# Power.net
KiCad netlist of a schematic drawn in Altium Designer
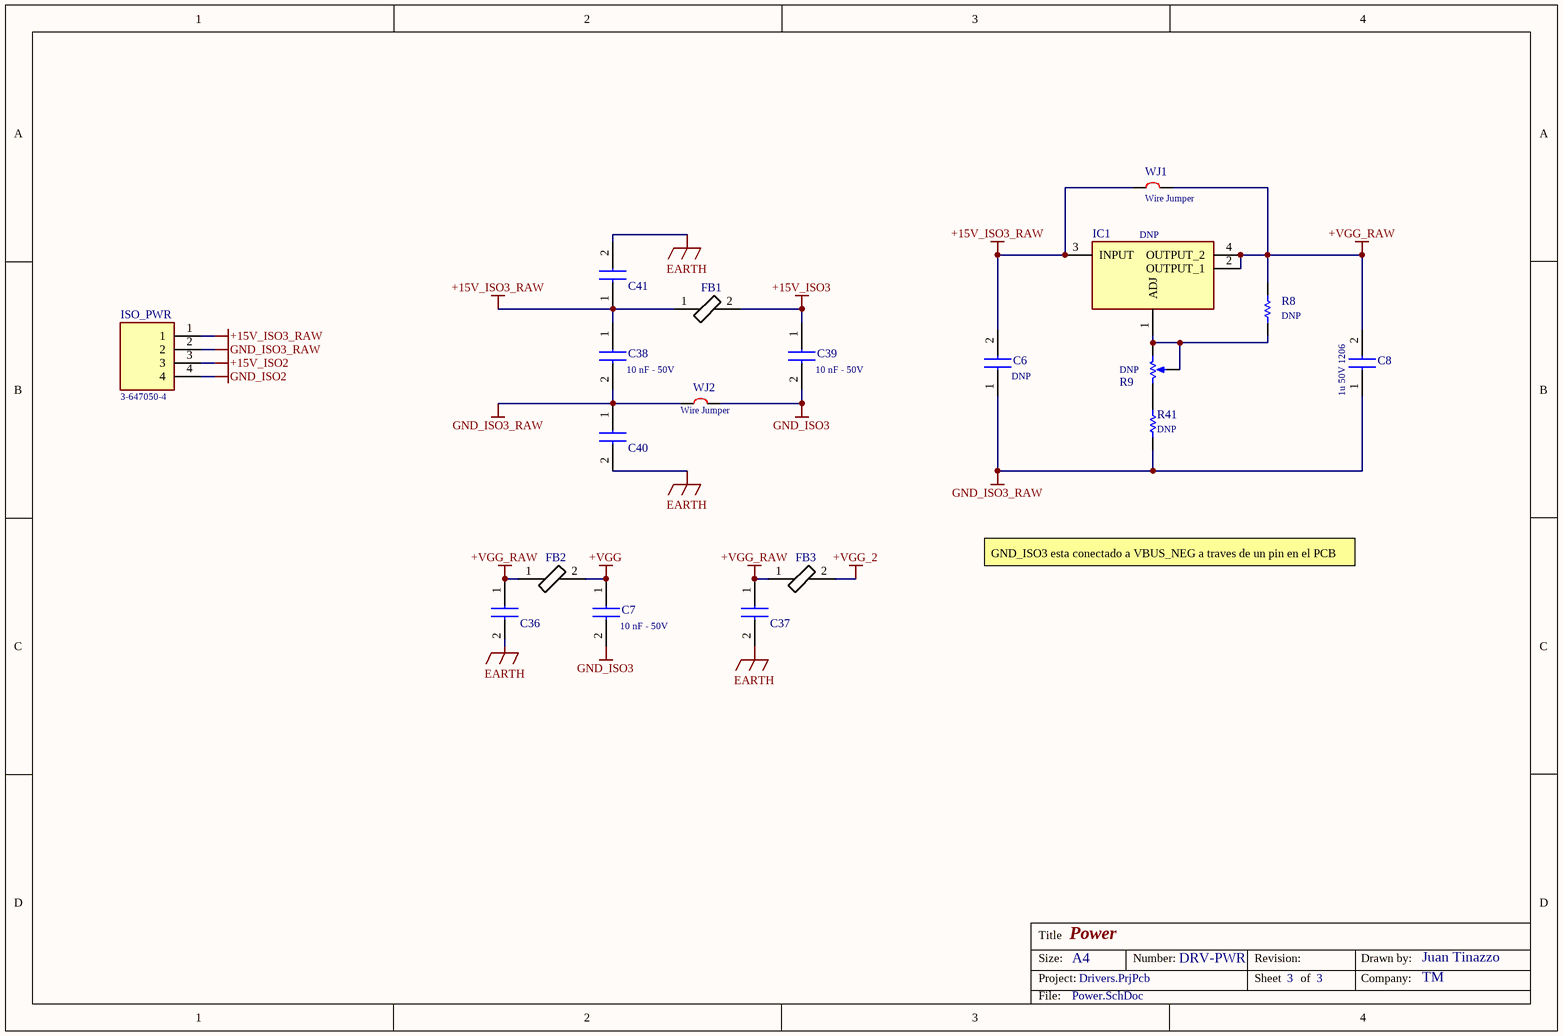
[diagram p0: Power.SchDoc]

(export (version "E")
  (design (tool "Eeschema 10.0.6"))
  (components
    (comp (ref "C6")
      (value "DNP")
      (footprint "SamacSys:CAPC3216X180N")
      (description "Capacitor")
      (fields
        (field (name "MANUFACTURER_PART_NUMBER") "C3216X7R1H105K160AE")
        (field (name "MOUSER PART NUMBER") "810-C3216X7R1H105KST")
      )
      (libsource (lib "*") (part "C3216X7R1H105K160AE"))
    )
    (comp (ref "C7")
      (value "10 nF - 50V")
      (footprint "CAPC1608X90N")
      (description "Capacitor")
      (fields
        (field (name "MANUFACTURER_PART_NUMBER") "CGA3E2X7R1H103K080AA")
        (field (name "MOUSER PART NUMBER") "810-CGA3E2X7R1H103K")
      )
      (libsource (lib "SamacSys") (part "CGA3E2X7R1H103K080AA"))
    )
    (comp (ref "C8")
      (value "1u 50V 1206")
      (footprint "SamacSys:CAPC3216X180N")
      (description "Capacitor")
      (fields
        (field (name "MANUFACTURER_PART_NUMBER") "C3216X7R1H105K160AE")
        (field (name "MOUSER PART NUMBER") "810-C3216X7R1H105KST")
      )
      (libsource (lib "*") (part "C3216X7R1H105K160AE"))
    )
    (comp (ref "C36")
      (value "C1206C102KGRACAUTO")
      (footprint "C1206")
      (description "Capacitor")
      (fields (field (name "MOUSER PART NUMBER") "80-C1206C102KGRAUTO"))
      (libsource (lib "SamacSys") (part "C1206C102KGRACAUTO"))
    )
    (comp (ref "C37")
      (value "C1206C102KGRACAUTO")
      (footprint "C1206")
      (description "Capacitor")
      (fields (field (name "MOUSER PART NUMBER") "80-C1206C102KGRAUTO"))
      (libsource (lib "SamacSys") (part "C1206C102KGRACAUTO"))
    )
    (comp (ref "C38")
      (value "10 nF - 50V")
      (footprint "CAPC1608X90N")
      (description "Capacitor")
      (fields
        (field (name "MANUFACTURER_PART_NUMBER") "CGA3E2X7R1H103K080AA")
        (field (name "MOUSER PART NUMBER") "810-CGA3E2X7R1H103K")
      )
      (libsource (lib "SamacSys") (part "CGA3E2X7R1H103K080AA"))
    )
    (comp (ref "C39")
      (value "10 nF - 50V")
      (footprint "CAPC1608X90N")
      (description "Capacitor")
      (fields
        (field (name "MANUFACTURER_PART_NUMBER") "CGA3E2X7R1H103K080AA")
        (field (name "MOUSER PART NUMBER") "810-CGA3E2X7R1H103K")
      )
      (libsource (lib "SamacSys") (part "CGA3E2X7R1H103K080AA"))
    )
    (comp (ref "C40")
      (value "C1206C102KGRACAUTO")
      (footprint "C1206")
      (description "Capacitor")
      (fields (field (name "MOUSER PART NUMBER") "80-C1206C102KGRAUTO"))
      (libsource (lib "SamacSys") (part "C1206C102KGRACAUTO"))
    )
    (comp (ref "C41")
      (value "C1206C102KGRACAUTO")
      (footprint "C1206")
      (description "Capacitor")
      (fields (field (name "MOUSER PART NUMBER") "80-C1206C102KGRAUTO"))
      (libsource (lib "SamacSys") (part "C1206C102KGRACAUTO"))
    )
    (comp (ref "FB1")
      (value "78279220601")
      (footprint "SamacSys:BEADC2012X110N")
      (description "Ferrite Bead")
      (fields (field (name "MOUSER PART NUMBER") "710-78279220601"))
      (libsource (lib "SamacSys") (part "78279220601"))
    )
    (comp (ref "FB2")
      (value "78279220601")
      (footprint "SamacSys:BEADC2012X110N")
      (description "Ferrite Bead")
      (fields (field (name "MOUSER PART NUMBER") "710-78279220601"))
      (libsource (lib "SamacSys") (part "78279220601"))
    )
    (comp (ref "FB3")
      (value "78279220601")
      (footprint "SamacSys:BEADC2012X110N")
      (description "Ferrite Bead")
      (fields (field (name "MOUSER PART NUMBER") "710-78279220601"))
      (libsource (lib "SamacSys") (part "78279220601"))
    )
    (comp (ref "IC1")
      (value "DNP")
      (footprint "SamacSys:SOT230P700X180-4N")
      (description "Integrated Circuit")
      (fields
        (field (name "MANUFACTURER_PART_NUMBER") "NCP1117LPSTADT3G")
        (field (name "MOUSER PART NUMBER") "863-NCP1117LPSTADT3G")
      )
      (libsource (lib "SamacSys") (part "NCP1117LPSTADT3G"))
    )
    (comp (ref "ISO_PWR")
      (value "3-647050-4")
      (footprint "SamacSys:SHDR4W66P0X254_1X4_1016X635X1079P")
      (description "Connector")
      (fields (field (name "MOUSER PART NUMBER") "571-3-647050-4"))
      (libsource (lib "*") (part "3-647050-4"))
    )
    (comp (ref "R8")
      (value "DNP")
      (footprint "RESC1608X55N")
      (description "Resistor")
      (fields
        (field (name "MANUFACTURER_PART_NUMBER") "CRCW0603220RFKEAC")
        (field (name "MOUSER PART NUMBER") "71-CRCW0603220RFKEAC")
      )
      (libsource (lib "SamacSys") (part "CRCW0603220RFKEAC"))
    )
    (comp (ref "R9")
      (value "DNP")
      (footprint "SamacSys:3296W-1")
      (description "Resistor")
      (fields
        (field (name "MANUFACTURER_PART_NUMBER") "3296W-1-502LF")
        (field (name "MOUSER PART NUMBER") "652-3296W-1-502LF")
      )
      (libsource (lib "SamacSys") (part "3296W-1-502LF"))
    )
    (comp (ref "R41")
      (value "DNP")
      (footprint "SamacSys:RESC1608X55N")
      (description "Resistor")
      (fields
        (field (name "MANUFACTURER_PART_NUMBER") "ERJ-3EKF6800V")
        (field (name "MOUSER PART NUMBER") "667-ERJ-3EKF6800V")
      )
      (libsource (lib "SamacSys") (part "ERJ-3EKF6800V"))
    )
    (comp (ref "WJ1")
      (value "Wire Jumper")
      (fields (field (name "MANUFACTURER_PART_NUMBER") "Wire"))
      (libsource (lib "SamacSys") (part "Wire Jumper"))
    )
    (comp (ref "WJ2")
      (value "Wire Jumper")
      (fields (field (name "MANUFACTURER_PART_NUMBER") "Wire"))
      (libsource (lib "SamacSys") (part "Wire Jumper"))
    )
  )
  (nets
    (net (code "1") (name "+15V_ISO2") (class "Default")
      (node (ref "ISO_PWR") (pin "3") (pinfunction "3_3") (pintype "passive"))
    )
    (net (code "2") (name "+15V_ISO3") (class "Default")
      (node (ref "C39") (pin "1") (pinfunction "1_1") (pintype "passive"))
      (node (ref "FB1") (pin "2") (pinfunction "2_2") (pintype "passive"))
    )
    (net (code "3") (name "+15V_ISO3_RAW") (class "Default")
      (node (ref "C38") (pin "1") (pinfunction "1_1") (pintype "passive"))
      (node (ref "C41") (pin "1") (pinfunction "1_1") (pintype "passive"))
      (node (ref "C6") (pin "2") (pinfunction "2_2") (pintype "passive"))
      (node (ref "FB1") (pin "1") (pinfunction "1_1") (pintype "passive"))
      (node (ref "IC1") (pin "3") (pinfunction "INPUT_3") (pintype "passive"))
      (node (ref "ISO_PWR") (pin "1") (pinfunction "1_1") (pintype "passive"))
      (node (ref "WJ1") (pin "0") (pinfunction "0_0") (pintype "passive"))
    )
    (net (code "4") (name "+VGG") (class "Default")
      (node (ref "C7") (pin "1") (pinfunction "1_1") (pintype "passive"))
      (node (ref "FB2") (pin "2") (pinfunction "2_2") (pintype "passive"))
    )
    (net (code "5") (name "+VGG_2") (class "Default")
      (node (ref "FB3") (pin "2") (pinfunction "2_2") (pintype "passive"))
    )
    (net (code "6") (name "+VGG_RAW") (class "Default")
      (node (ref "C36") (pin "1") (pinfunction "1_1") (pintype "passive"))
      (node (ref "C37") (pin "1") (pinfunction "1_1") (pintype "passive"))
      (node (ref "C8") (pin "2") (pinfunction "2_2") (pintype "passive"))
      (node (ref "FB2") (pin "1") (pinfunction "1_1") (pintype "passive"))
      (node (ref "FB3") (pin "1") (pinfunction "1_1") (pintype "passive"))
      (node (ref "IC1") (pin "2") (pinfunction "OUTPUT_1_2") (pintype "passive"))
      (node (ref "IC1") (pin "4") (pinfunction "OUTPUT_2_4") (pintype "passive"))
      (node (ref "R8") (pin "1") (pinfunction "1_1") (pintype "passive"))
      (node (ref "WJ1") (pin "1") (pinfunction "1_1") (pintype "passive"))
    )
    (net (code "7") (name "EARTH") (class "Default")
      (node (ref "C36") (pin "2") (pinfunction "2_2") (pintype "passive"))
      (node (ref "C37") (pin "2") (pinfunction "2_2") (pintype "passive"))
      (node (ref "C40") (pin "2") (pinfunction "2_2") (pintype "passive"))
      (node (ref "C41") (pin "2") (pinfunction "2_2") (pintype "passive"))
    )
    (net (code "8") (name "GND_ISO2") (class "Default")
      (node (ref "ISO_PWR") (pin "4") (pinfunction "4_4") (pintype "passive"))
    )
    (net (code "9") (name "GND_ISO3") (class "Default")
      (node (ref "C39") (pin "2") (pinfunction "2_2") (pintype "passive"))
      (node (ref "C7") (pin "2") (pinfunction "2_2") (pintype "passive"))
      (node (ref "WJ2") (pin "1") (pinfunction "1_1") (pintype "passive"))
    )
    (net (code "10") (name "GND_ISO3_RAW") (class "Default")
      (node (ref "C38") (pin "2") (pinfunction "2_2") (pintype "passive"))
      (node (ref "C40") (pin "1") (pinfunction "1_1") (pintype "passive"))
      (node (ref "C6") (pin "1") (pinfunction "1_1") (pintype "passive"))
      (node (ref "C8") (pin "1") (pinfunction "1_1") (pintype "passive"))
      (node (ref "ISO_PWR") (pin "2") (pinfunction "2_2") (pintype "passive"))
      (node (ref "R41") (pin "2") (pinfunction "2_2") (pintype "passive"))
      (node (ref "WJ2") (pin "0") (pinfunction "0_0") (pintype "passive"))
    )
    (net (code "11") (name "Net-(IC1-ADJ)") (class "Default")
      (node (ref "IC1") (pin "1") (pinfunction "ADJ_1") (pintype "passive"))
      (node (ref "R8") (pin "2") (pinfunction "2_2") (pintype "passive"))
      (node (ref "R9") (pin "1") (pinfunction "TOP_1") (pintype "passive"))
      (node (ref "R9") (pin "2") (pinfunction "BOT_2") (pintype "passive"))
    )
    (net (code "12") (name "Net-(R9-TAP)") (class "Default")
      (node (ref "R41") (pin "1") (pinfunction "1_1") (pintype "passive"))
      (node (ref "R9") (pin "3") (pinfunction "TAP_3") (pintype "passive"))
    )
  )
)
